# linear_supply3_smd.net
KiCad netlist of a schematic drawn in EAGLE
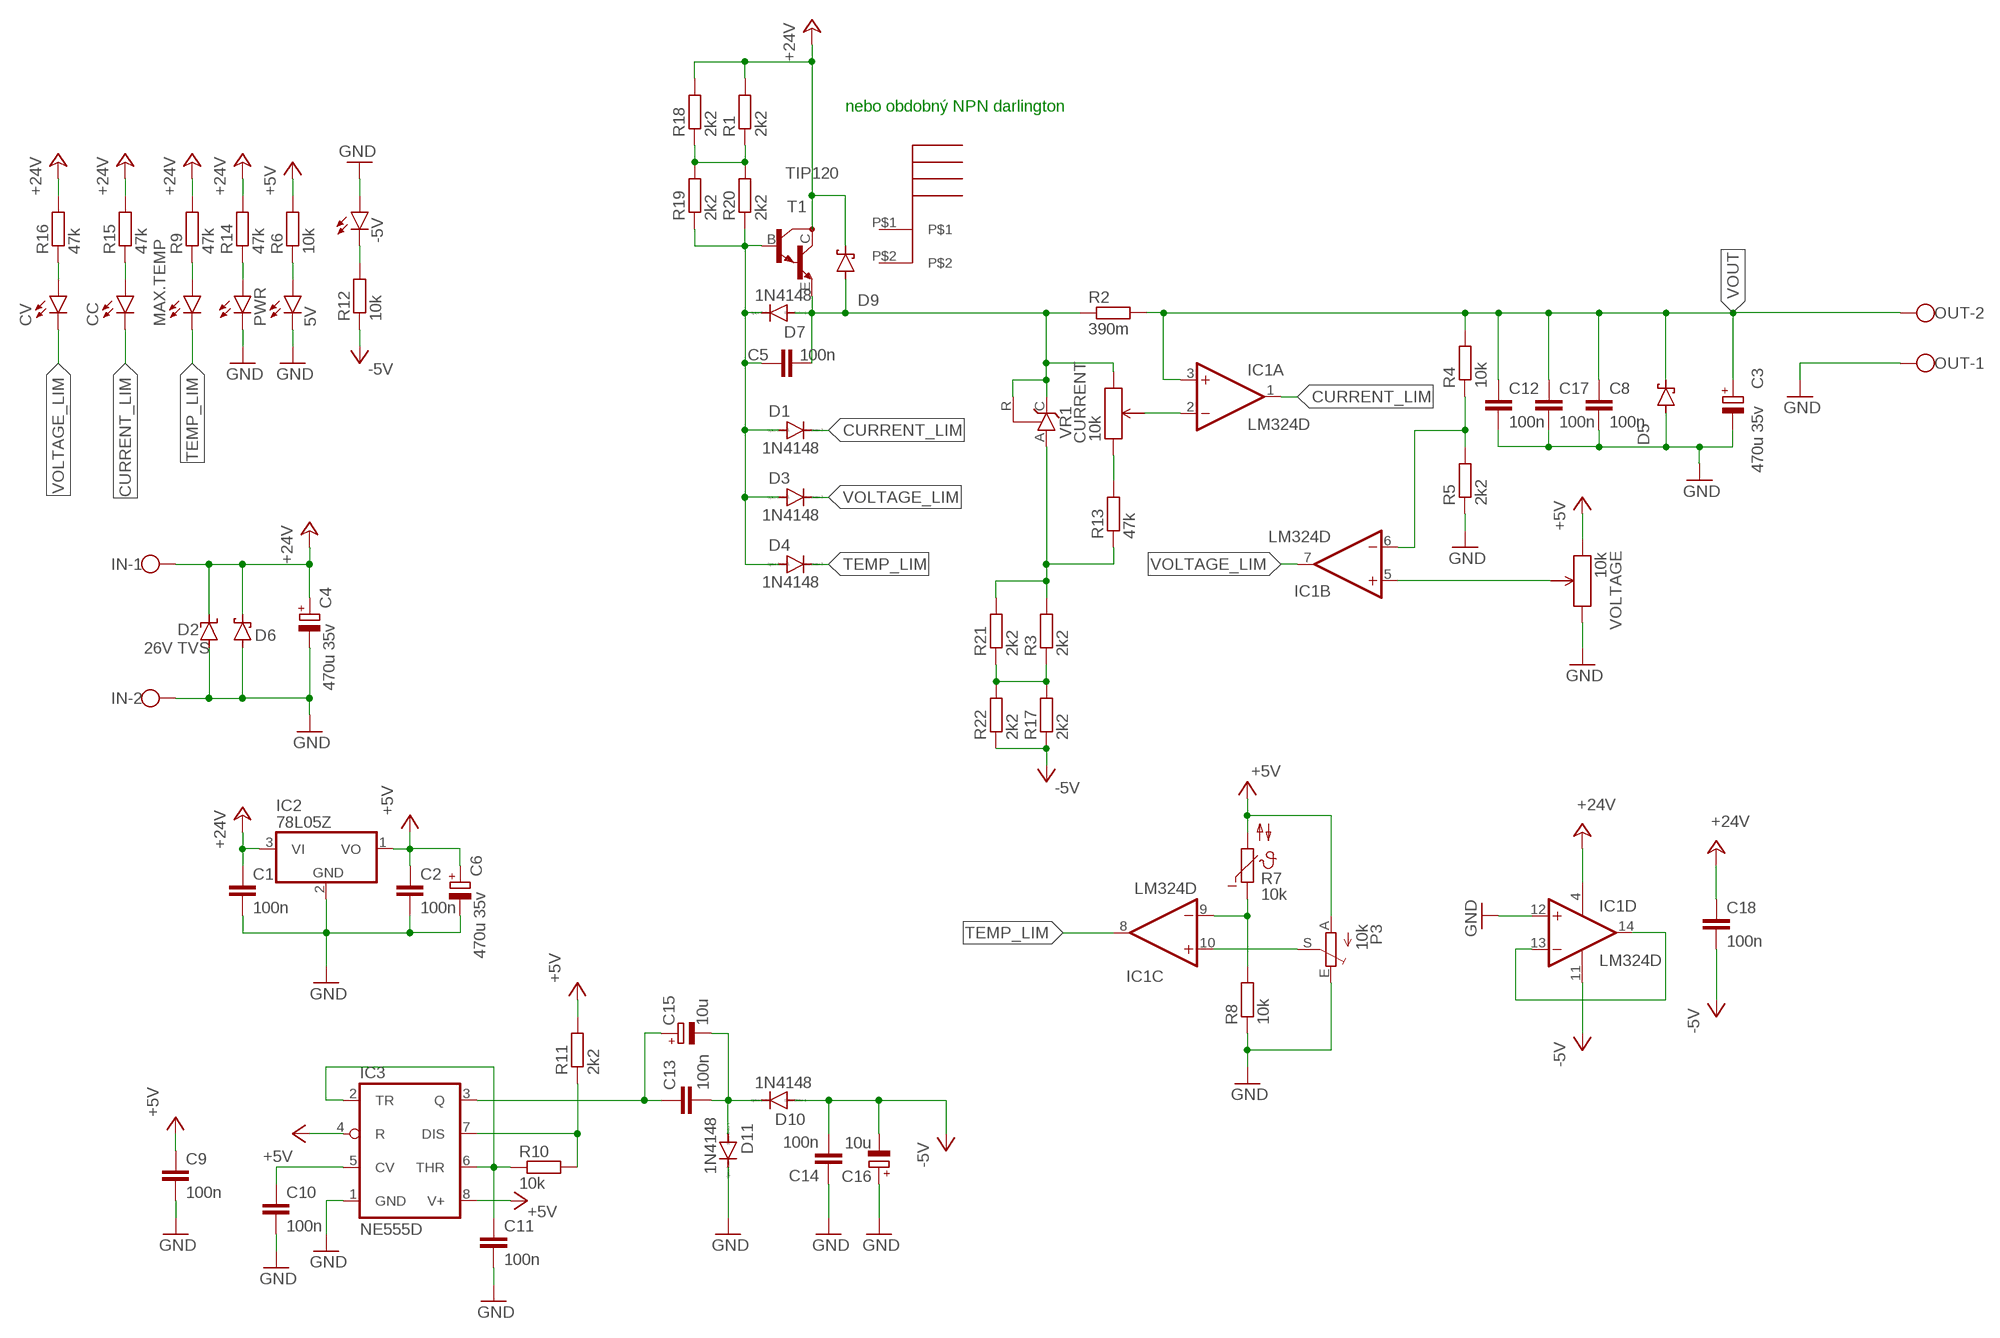
[diagram p0: schematic, sheet 1]

(export (version "E")
  (design (tool "Eeschema 10.0.6"))
  (components
    (comp (ref "-5V")
      (value "LEDCHIP-LED0805")
      (footprint "eagle-import:CHIP-LED0805")
      (libsource (lib "eagle-import") (part "LEDCHIP-LED0805"))
    )
    (comp (ref "5V")
      (value "LEDCHIP-LED0805")
      (footprint "eagle-import:CHIP-LED0805")
      (libsource (lib "eagle-import") (part "LEDCHIP-LED0805"))
    )
    (comp (ref "C1")
      (value "100n")
      (footprint "eagle-import:C0805")
      (libsource (lib "eagle-import") (part "C-EUC0805"))
    )
    (comp (ref "C2")
      (value "100n")
      (footprint "eagle-import:C0805")
      (libsource (lib "eagle-import") (part "C-EUC0805"))
    )
    (comp (ref "C3")
      (value "470u 35v")
      (footprint "eagle-import:E5-10,5")
      (libsource (lib "eagle-import") (part "CPOL-EUE5-10.5"))
    )
    (comp (ref "C4")
      (value "470u 35v")
      (footprint "eagle-import:E5-10,5")
      (libsource (lib "eagle-import") (part "CPOL-EUE5-10.5"))
    )
    (comp (ref "C5")
      (value "100n")
      (footprint "eagle-import:C0805")
      (libsource (lib "eagle-import") (part "C-EUC0805"))
    )
    (comp (ref "C6")
      (value "470u 35v")
      (footprint "eagle-import:E5-10,5")
      (libsource (lib "eagle-import") (part "CPOL-EUE5-10.5"))
    )
    (comp (ref "C8")
      (value "100n")
      (footprint "eagle-import:C050-050X075")
      (libsource (lib "eagle-import") (part "C-EU050-050X075"))
    )
    (comp (ref "C9")
      (value "100n")
      (footprint "eagle-import:C0805")
      (libsource (lib "eagle-import") (part "C-EUC0805"))
    )
    (comp (ref "C10")
      (value "100n")
      (footprint "eagle-import:C0805")
      (libsource (lib "eagle-import") (part "C-EUC0805"))
    )
    (comp (ref "C11")
      (value "100n")
      (footprint "eagle-import:C0805")
      (libsource (lib "eagle-import") (part "C-EUC0805"))
    )
    (comp (ref "C12")
      (value "100n")
      (footprint "eagle-import:C1206")
      (libsource (lib "eagle-import") (part "C-EUC1206"))
    )
    (comp (ref "C13")
      (value "100n")
      (footprint "eagle-import:C0805")
      (libsource (lib "eagle-import") (part "C-EUC0805"))
    )
    (comp (ref "C14")
      (value "100n")
      (footprint "eagle-import:C0805")
      (libsource (lib "eagle-import") (part "C-EUC0805"))
    )
    (comp (ref "C15")
      (value "10u")
      (footprint "eagle-import:E2,5-6")
      (libsource (lib "eagle-import") (part "CPOL-EUE2.5-6"))
    )
    (comp (ref "C16")
      (value "10u")
      (footprint "eagle-import:E2,5-6")
      (libsource (lib "eagle-import") (part "CPOL-EUE2.5-6"))
    )
    (comp (ref "C17")
      (value "100n")
      (footprint "eagle-import:C1206")
      (libsource (lib "eagle-import") (part "C-EUC1206"))
    )
    (comp (ref "C18")
      (value "100n")
      (footprint "eagle-import:C0805")
      (libsource (lib "eagle-import") (part "C-EUC0805"))
    )
    (comp (ref "CC")
      (value "LEDCHIP-LED0805")
      (footprint "eagle-import:CHIP-LED0805")
      (libsource (lib "eagle-import") (part "LEDCHIP-LED0805"))
    )
    (comp (ref "CURRENT")
      (value "10k")
      (footprint "eagle-import:THRU_PCW_POT")
      (libsource (lib "eagle-import") (part "THRU_PCB_POTKASO1"))
    )
    (comp (ref "CV")
      (value "LEDCHIP-LED0805")
      (footprint "eagle-import:CHIP-LED0805")
      (libsource (lib "eagle-import") (part "LEDCHIP-LED0805"))
    )
    (comp (ref "D1")
      (value "1N4148")
      (footprint "eagle-import:SOD80C")
      (libsource (lib "eagle-import") (part "PMLL4150"))
    )
    (comp (ref "D2")
      (value "26V TVS")
      (footprint "eagle-import:SMBJ")
      (libsource (lib "eagle-import") (part "SUPPRESSOR-SMBJ"))
    )
    (comp (ref "D3")
      (value "1N4148")
      (footprint "eagle-import:SOD80C")
      (libsource (lib "eagle-import") (part "PMLL4150"))
    )
    (comp (ref "D4")
      (value "1N4148")
      (footprint "eagle-import:SOD80C")
      (libsource (lib "eagle-import") (part "PMLL4150"))
    )
    (comp (ref "D5")
      (value "SCHOTTKY-DIODESMC")
      (footprint "eagle-import:SMC")
      (libsource (lib "eagle-import") (part "SCHOTTKY-DIODESMC"))
    )
    (comp (ref "D6")
      (value "SCHOTTKY-DIODESMC")
      (footprint "eagle-import:SMC")
      (libsource (lib "eagle-import") (part "SCHOTTKY-DIODESMC"))
    )
    (comp (ref "D7")
      (value "1N4148")
      (footprint "eagle-import:SOD80C")
      (libsource (lib "eagle-import") (part "PMLL4150"))
    )
    (comp (ref "D9")
      (value "SCHOTTKY-DIODESMC")
      (footprint "eagle-import:SMC")
      (libsource (lib "eagle-import") (part "SCHOTTKY-DIODESMC"))
    )
    (comp (ref "D10")
      (value "1N4148")
      (footprint "eagle-import:SOD80C")
      (libsource (lib "eagle-import") (part "PMLL4150"))
    )
    (comp (ref "D11")
      (value "1N4148")
      (footprint "eagle-import:SOD80C")
      (libsource (lib "eagle-import") (part "PMLL4150"))
    )
    (comp (ref "IC1")
      (value "LM324D")
      (footprint "eagle-import:SO14")
      (libsource (lib "eagle-import") (part "LM324D"))
    )
    (comp (ref "IC2")
      (value "78L05Z")
      (footprint "eagle-import:TO92")
      (libsource (lib "eagle-import") (part "78ZL05"))
    )
    (comp (ref "IC3")
      (value "NE555D")
      (footprint "eagle-import:SO08")
      (libsource (lib "eagle-import") (part "555DNE"))
    )
    (comp (ref "IN")
      (value "W237-102")
      (footprint "eagle-import:W237-102")
      (fields (field (name "MPN") "237-102"))
      (libsource (lib "eagle-import") (part "W237-102"))
    )
    (comp (ref "MAX.TEMP")
      (value "LEDCHIP-LED0805")
      (footprint "eagle-import:CHIP-LED0805")
      (libsource (lib "eagle-import") (part "LEDCHIP-LED0805"))
    )
    (comp (ref "OUT")
      (value "W237-102")
      (footprint "eagle-import:W237-102")
      (fields (field (name "MPN") "237-102"))
      (libsource (lib "eagle-import") (part "W237-102"))
    )
    (comp (ref "P3")
      (value "10k")
      (footprint "eagle-import:CA6V")
      (libsource (lib "eagle-import") (part "TRIM_EU-CA6V"))
    )
    (comp (ref "PWR")
      (value "LEDCHIP-LED0805")
      (footprint "eagle-import:CHIP-LED0805")
      (libsource (lib "eagle-import") (part "LEDCHIP-LED0805"))
    )
    (comp (ref "R1")
      (value "2k2")
      (footprint "eagle-import:R0805")
      (libsource (lib "eagle-import") (part "R-EU_R0805"))
    )
    (comp (ref "R2")
      (value "390m")
      (footprint "eagle-import:0411_12")
      (libsource (lib "eagle-import") (part "R-EU_0411/12"))
    )
    (comp (ref "R3")
      (value "2k2")
      (footprint "eagle-import:R0805")
      (libsource (lib "eagle-import") (part "R-EU_R0805"))
    )
    (comp (ref "R4")
      (value "10k")
      (footprint "eagle-import:R0805")
      (libsource (lib "eagle-import") (part "R-EU_R0805"))
    )
    (comp (ref "R5")
      (value "2k2")
      (footprint "eagle-import:R0805")
      (libsource (lib "eagle-import") (part "R-EU_R0805"))
    )
    (comp (ref "R6")
      (value "10k")
      (footprint "eagle-import:R0805")
      (libsource (lib "eagle-import") (part "R-EU_R0805"))
    )
    (comp (ref "R7")
      (value "10k")
      (footprint "eagle-import:P642")
      (libsource (lib "eagle-import") (part "V642"))
    )
    (comp (ref "R8")
      (value "10k")
      (footprint "eagle-import:R0805")
      (libsource (lib "eagle-import") (part "R-EU_R0805"))
    )
    (comp (ref "R9")
      (value "47k")
      (footprint "eagle-import:R0805")
      (libsource (lib "eagle-import") (part "R-EU_R0805"))
    )
    (comp (ref "R10")
      (value "10k")
      (footprint "eagle-import:R0805")
      (libsource (lib "eagle-import") (part "R-EU_R0805"))
    )
    (comp (ref "R11")
      (value "2k2")
      (footprint "eagle-import:R0805")
      (libsource (lib "eagle-import") (part "R-EU_R0805"))
    )
    (comp (ref "R12")
      (value "10k")
      (footprint "eagle-import:R0805")
      (libsource (lib "eagle-import") (part "R-EU_R0805"))
    )
    (comp (ref "R13")
      (value "47k")
      (footprint "eagle-import:R0805")
      (libsource (lib "eagle-import") (part "R-EU_R0805"))
    )
    (comp (ref "R14")
      (value "47k")
      (footprint "eagle-import:R0805")
      (libsource (lib "eagle-import") (part "R-EU_R0805"))
    )
    (comp (ref "R15")
      (value "47k")
      (footprint "eagle-import:R0805")
      (libsource (lib "eagle-import") (part "R-EU_R0805"))
    )
    (comp (ref "R16")
      (value "47k")
      (footprint "eagle-import:R0805")
      (libsource (lib "eagle-import") (part "R-EU_R0805"))
    )
    (comp (ref "R17")
      (value "2k2")
      (footprint "eagle-import:R0805")
      (libsource (lib "eagle-import") (part "R-EU_R0805"))
    )
    (comp (ref "R18")
      (value "2k2")
      (footprint "eagle-import:R0805")
      (libsource (lib "eagle-import") (part "R-EU_R0805"))
    )
    (comp (ref "R19")
      (value "2k2")
      (footprint "eagle-import:R0805")
      (libsource (lib "eagle-import") (part "R-EU_R0805"))
    )
    (comp (ref "R20")
      (value "2k2")
      (footprint "eagle-import:R0805")
      (libsource (lib "eagle-import") (part "R-EU_R0805"))
    )
    (comp (ref "R21")
      (value "2k2")
      (footprint "eagle-import:R0805")
      (libsource (lib "eagle-import") (part "R-EU_R0805"))
    )
    (comp (ref "R22")
      (value "2k2")
      (footprint "eagle-import:R0805")
      (libsource (lib "eagle-import") (part "R-EU_R0805"))
    )
    (comp (ref "T1")
      (value "TIP120")
      (footprint "eagle-import:SOT93")
      (libsource (lib "eagle-import") (part "BDV65"))
    )
    (comp (ref "U$1")
      (value "RAD-DY-KY/3")
      (footprint "eagle-import:RAD-DY-KY_3HEATSINK")
      (libsource (lib "eagle-import") (part "RAD-DY-KY/3"))
    )
    (comp (ref "VOLTAGE")
      (value "10k")
      (footprint "eagle-import:THRU_PCW_POT")
      (fields (field (name "SPICEPREFIX") "J"))
      (libsource (lib "eagle-import") (part "THRU_PCB_POTKASO1"))
    )
    (comp (ref "VR1")
      (value "TL431CLP")
      (footprint "eagle-import:TO92-CLP")
      (libsource (lib "eagle-import") (part "TL431CLP"))
    )
  )
  (nets
    (net (code "1") (name "+5V") (class "Default")
      (node (ref "C2") (pin "1") (pinfunction "1_1") (pintype "passive"))
      (node (ref "C6") (pin "+") (pinfunction "+_+") (pintype "passive"))
      (node (ref "C9") (pin "1") (pinfunction "1_1") (pintype "passive"))
      (node (ref "IC2") (pin "1") (pinfunction "VO_1") (pintype "passive"))
      (node (ref "IC3") (pin "4") (pinfunction "R_4") (pintype "input"))
      (node (ref "IC3") (pin "8") (pinfunction "V+_8") (pintype "power_in"))
      (node (ref "P3") (pin "A") (pinfunction "A_A") (pintype "passive"))
      (node (ref "R11") (pin "2") (pinfunction "2_2") (pintype "passive"))
      (node (ref "R6") (pin "2") (pinfunction "2_2") (pintype "passive"))
      (node (ref "R7") (pin "2") (pinfunction "2_2") (pintype "passive"))
      (node (ref "VOLTAGE") (pin "P$1") (pinfunction "1_P$1") (pintype "bidirectional"))
    )
    (net (code "2") (name "+24V") (class "Default")
      (node (ref "C1") (pin "1") (pinfunction "1_1") (pintype "passive"))
      (node (ref "C18") (pin "1") (pinfunction "1_1") (pintype "passive"))
      (node (ref "C4") (pin "+") (pinfunction "+_+") (pintype "passive"))
      (node (ref "D2") (pin "C") (pinfunction "C_C") (pintype "passive"))
      (node (ref "D6") (pin "C") (pinfunction "C_C") (pintype "passive"))
      (node (ref "D9") (pin "C") (pinfunction "C_C") (pintype "passive"))
      (node (ref "IC1") (pin "4") (pinfunction "V+_4") (pintype "power_in"))
      (node (ref "IC2") (pin "3") (pinfunction "VI_3") (pintype "input"))
      (node (ref "IN") (pin "1") (pinfunction "KL_1") (pintype "passive"))
      (node (ref "R1") (pin "2") (pinfunction "2_2") (pintype "passive"))
      (node (ref "R14") (pin "2") (pinfunction "2_2") (pintype "passive"))
      (node (ref "R15") (pin "2") (pinfunction "2_2") (pintype "passive"))
      (node (ref "R16") (pin "2") (pinfunction "2_2") (pintype "passive"))
      (node (ref "R18") (pin "2") (pinfunction "2_2") (pintype "passive"))
      (node (ref "R9") (pin "2") (pinfunction "2_2") (pintype "passive"))
      (node (ref "T1") (pin "C") (pinfunction "C_C") (pintype "passive"))
    )
    (net (code "3") (name "-5V") (class "Default")
      (node (ref "C14") (pin "2") (pinfunction "2_2") (pintype "passive"))
      (node (ref "C16") (pin "-") (pinfunction "-_-") (pintype "passive"))
      (node (ref "C18") (pin "2") (pinfunction "2_2") (pintype "passive"))
      (node (ref "D10") (pin "A") (pinfunction "A_A") (pintype "passive"))
      (node (ref "IC1") (pin "11") (pinfunction "V-_11") (pintype "power_in"))
      (node (ref "R12") (pin "1") (pinfunction "1_1") (pintype "passive"))
      (node (ref "R17") (pin "1") (pinfunction "1_1") (pintype "passive"))
      (node (ref "R22") (pin "1") (pinfunction "1_1") (pintype "passive"))
    )
    (net (code "4") (name "CURRENT_LIM") (class "Default")
      (node (ref "CC") (pin "C") (pinfunction "C_C") (pintype "passive"))
      (node (ref "D1") (pin "C") (pinfunction "C_C") (pintype "passive"))
      (node (ref "IC1") (pin "1") (pinfunction "OUT_1") (pintype "output"))
    )
    (net (code "5") (name "GND") (class "Default")
      (node (ref "-5V") (pin "A") (pinfunction "A_A") (pintype "passive"))
      (node (ref "5V") (pin "C") (pinfunction "C_C") (pintype "passive"))
      (node (ref "C1") (pin "2") (pinfunction "2_2") (pintype "passive"))
      (node (ref "C10") (pin "2") (pinfunction "2_2") (pintype "passive"))
      (node (ref "C11") (pin "2") (pinfunction "2_2") (pintype "passive"))
      (node (ref "C12") (pin "2") (pinfunction "2_2") (pintype "passive"))
      (node (ref "C14") (pin "1") (pinfunction "1_1") (pintype "passive"))
      (node (ref "C16") (pin "+") (pinfunction "+_+") (pintype "passive"))
      (node (ref "C17") (pin "2") (pinfunction "2_2") (pintype "passive"))
      (node (ref "C2") (pin "2") (pinfunction "2_2") (pintype "passive"))
      (node (ref "C3") (pin "-") (pinfunction "-_-") (pintype "passive"))
      (node (ref "C4") (pin "-") (pinfunction "-_-") (pintype "passive"))
      (node (ref "C6") (pin "-") (pinfunction "-_-") (pintype "passive"))
      (node (ref "C8") (pin "2") (pinfunction "2_2") (pintype "passive"))
      (node (ref "C9") (pin "2") (pinfunction "2_2") (pintype "passive"))
      (node (ref "D11") (pin "C") (pinfunction "C_C") (pintype "passive"))
      (node (ref "D2") (pin "A") (pinfunction "A_A") (pintype "passive"))
      (node (ref "D5") (pin "A") (pinfunction "A_A") (pintype "passive"))
      (node (ref "D6") (pin "A") (pinfunction "A_A") (pintype "passive"))
      (node (ref "IC1") (pin "12") (pinfunction "+IN_12") (pintype "input"))
      (node (ref "IC2") (pin "2") (pinfunction "GND_2") (pintype "passive"))
      (node (ref "IC3") (pin "1") (pinfunction "GND_1") (pintype "power_in"))
      (node (ref "IN") (pin "2") (pinfunction "KL_2") (pintype "passive"))
      (node (ref "OUT") (pin "1") (pinfunction "KL_1") (pintype "passive"))
      (node (ref "P3") (pin "E") (pinfunction "E_E") (pintype "passive"))
      (node (ref "PWR") (pin "C") (pinfunction "C_C") (pintype "passive"))
      (node (ref "R5") (pin "1") (pinfunction "1_1") (pintype "passive"))
      (node (ref "R8") (pin "1") (pinfunction "1_1") (pintype "passive"))
      (node (ref "VOLTAGE") (pin "P$3") (pinfunction "3_P$3") (pintype "bidirectional"))
    )
    (net (code "6") (name "Net-(-5V-PadC)") (class "Default")
      (node (ref "-5V") (pin "C") (pinfunction "C_C") (pintype "passive"))
      (node (ref "R12") (pin "2") (pinfunction "2_2") (pintype "passive"))
    )
    (net (code "7") (name "Net-(5V-PadA)") (class "Default")
      (node (ref "5V") (pin "A") (pinfunction "A_A") (pintype "passive"))
      (node (ref "R6") (pin "1") (pinfunction "1_1") (pintype "passive"))
    )
    (net (code "8") (name "Net-(C5-Pad1)") (class "Default")
      (node (ref "C5") (pin "1") (pinfunction "1_1") (pintype "passive"))
      (node (ref "D1") (pin "A") (pinfunction "A_A") (pintype "passive"))
      (node (ref "D3") (pin "A") (pinfunction "A_A") (pintype "passive"))
      (node (ref "D4") (pin "A") (pinfunction "A_A") (pintype "passive"))
      (node (ref "D7") (pin "C") (pinfunction "C_C") (pintype "passive"))
      (node (ref "R19") (pin "1") (pinfunction "1_1") (pintype "passive"))
      (node (ref "R20") (pin "1") (pinfunction "1_1") (pintype "passive"))
      (node (ref "T1") (pin "B") (pinfunction "B_B") (pintype "passive"))
    )
    (net (code "9") (name "Net-(C13-Pad2)") (class "Default")
      (node (ref "C13") (pin "2") (pinfunction "2_2") (pintype "passive"))
      (node (ref "C15") (pin "-") (pinfunction "-_-") (pintype "passive"))
      (node (ref "D10") (pin "C") (pinfunction "C_C") (pintype "passive"))
      (node (ref "D11") (pin "A") (pinfunction "A_A") (pintype "passive"))
    )
    (net (code "10") (name "Net-(CC-PadA)") (class "Default")
      (node (ref "CC") (pin "A") (pinfunction "A_A") (pintype "passive"))
      (node (ref "R15") (pin "1") (pinfunction "1_1") (pintype "passive"))
    )
    (net (code "11") (name "Net-(CURRENT-1)") (class "Default")
      (node (ref "CURRENT") (pin "P$1") (pinfunction "1_P$1") (pintype "bidirectional"))
      (node (ref "R13") (pin "2") (pinfunction "2_2") (pintype "passive"))
    )
    (net (code "12") (name "Net-(CURRENT-2)") (class "Default")
      (node (ref "CURRENT") (pin "P$2") (pinfunction "2_P$2") (pintype "bidirectional"))
      (node (ref "IC1") (pin "2") (pinfunction "-IN_2") (pintype "input"))
    )
    (net (code "13") (name "Net-(CURRENT-3)") (class "Default")
      (node (ref "C5") (pin "2") (pinfunction "2_2") (pintype "passive"))
      (node (ref "CURRENT") (pin "P$3") (pinfunction "3_P$3") (pintype "bidirectional"))
      (node (ref "D7") (pin "A") (pinfunction "A_A") (pintype "passive"))
      (node (ref "D9") (pin "A") (pinfunction "A_A") (pintype "passive"))
      (node (ref "R2") (pin "1") (pinfunction "1_1") (pintype "passive"))
      (node (ref "T1") (pin "E") (pinfunction "E_E") (pintype "passive"))
      (node (ref "VR1") (pin "C") (pinfunction "C_C") (pintype "passive"))
      (node (ref "VR1") (pin "R") (pinfunction "R_R") (pintype "passive"))
    )
    (net (code "14") (name "Net-(CV-PadA)") (class "Default")
      (node (ref "CV") (pin "A") (pinfunction "A_A") (pintype "passive"))
      (node (ref "R16") (pin "1") (pinfunction "1_1") (pintype "passive"))
    )
    (net (code "15") (name "Net-(IC1B-+IN)") (class "Default")
      (node (ref "IC1") (pin "5") (pinfunction "+IN_5") (pintype "input"))
      (node (ref "VOLTAGE") (pin "P$2") (pinfunction "2_P$2") (pintype "bidirectional"))
    )
    (net (code "16") (name "Net-(IC1B--IN)") (class "Default")
      (node (ref "IC1") (pin "6") (pinfunction "-IN_6") (pintype "input"))
      (node (ref "R4") (pin "1") (pinfunction "1_1") (pintype "passive"))
      (node (ref "R5") (pin "2") (pinfunction "2_2") (pintype "passive"))
    )
    (net (code "17") (name "Net-(IC1C-+IN)") (class "Default")
      (node (ref "IC1") (pin "10") (pinfunction "+IN_10") (pintype "input"))
      (node (ref "P3") (pin "S") (pinfunction "S_S") (pintype "passive"))
    )
    (net (code "18") (name "Net-(IC1C--IN)") (class "Default")
      (node (ref "IC1") (pin "9") (pinfunction "-IN_9") (pintype "input"))
      (node (ref "R7") (pin "1") (pinfunction "1_1") (pintype "passive"))
      (node (ref "R8") (pin "2") (pinfunction "2_2") (pintype "passive"))
    )
    (net (code "19") (name "Net-(IC1D--IN)") (class "Default")
      (node (ref "IC1") (pin "13") (pinfunction "-IN_13") (pintype "input"))
      (node (ref "IC1") (pin "14") (pinfunction "OUT_14") (pintype "output"))
    )
    (net (code "20") (name "Net-(IC3-CV)") (class "Default")
      (node (ref "C10") (pin "1") (pinfunction "1_1") (pintype "passive"))
      (node (ref "IC3") (pin "5") (pinfunction "CV_5") (pintype "input"))
    )
    (net (code "21") (name "Net-(IC3-DIS)") (class "Default")
      (node (ref "IC3") (pin "7") (pinfunction "DIS_7") (pintype "input"))
      (node (ref "R10") (pin "2") (pinfunction "2_2") (pintype "passive"))
      (node (ref "R11") (pin "1") (pinfunction "1_1") (pintype "passive"))
    )
    (net (code "22") (name "Net-(IC3-Q)") (class "Default")
      (node (ref "C13") (pin "1") (pinfunction "1_1") (pintype "passive"))
      (node (ref "C15") (pin "+") (pinfunction "+_+") (pintype "passive"))
      (node (ref "IC3") (pin "3") (pinfunction "Q_3") (pintype "output"))
    )
    (net (code "23") (name "Net-(IC3-THR)") (class "Default")
      (node (ref "C11") (pin "1") (pinfunction "1_1") (pintype "passive"))
      (node (ref "IC3") (pin "2") (pinfunction "TR_2") (pintype "input"))
      (node (ref "IC3") (pin "6") (pinfunction "THR_6") (pintype "input"))
      (node (ref "R10") (pin "1") (pinfunction "1_1") (pintype "passive"))
    )
    (net (code "24") (name "Net-(MAX.TEMP-PadA)") (class "Default")
      (node (ref "MAX.TEMP") (pin "A") (pinfunction "A_A") (pintype "passive"))
      (node (ref "R9") (pin "1") (pinfunction "1_1") (pintype "passive"))
    )
    (net (code "25") (name "Net-(PWR-PadA)") (class "Default")
      (node (ref "PWR") (pin "A") (pinfunction "A_A") (pintype "passive"))
      (node (ref "R14") (pin "1") (pinfunction "1_1") (pintype "passive"))
    )
    (net (code "26") (name "Net-(R1-Pad1)") (class "Default")
      (node (ref "R1") (pin "1") (pinfunction "1_1") (pintype "passive"))
      (node (ref "R18") (pin "1") (pinfunction "1_1") (pintype "passive"))
      (node (ref "R19") (pin "2") (pinfunction "2_2") (pintype "passive"))
      (node (ref "R20") (pin "2") (pinfunction "2_2") (pintype "passive"))
    )
    (net (code "27") (name "Net-(R13-Pad1)") (class "Default")
      (node (ref "R13") (pin "1") (pinfunction "1_1") (pintype "passive"))
      (node (ref "R21") (pin "2") (pinfunction "2_2") (pintype "passive"))
      (node (ref "R3") (pin "2") (pinfunction "2_2") (pintype "passive"))
      (node (ref "VR1") (pin "A") (pinfunction "A_A") (pintype "passive"))
    )
    (net (code "28") (name "Net-(R17-Pad2)") (class "Default")
      (node (ref "R17") (pin "2") (pinfunction "2_2") (pintype "passive"))
      (node (ref "R21") (pin "1") (pinfunction "1_1") (pintype "passive"))
      (node (ref "R22") (pin "2") (pinfunction "2_2") (pintype "passive"))
      (node (ref "R3") (pin "1") (pinfunction "1_1") (pintype "passive"))
    )
    (net (code "29") (name "TEMP_LIM") (class "Default")
      (node (ref "D4") (pin "C") (pinfunction "C_C") (pintype "passive"))
      (node (ref "IC1") (pin "8") (pinfunction "OUT_8") (pintype "output"))
      (node (ref "MAX.TEMP") (pin "C") (pinfunction "C_C") (pintype "passive"))
    )
    (net (code "30") (name "VOLTAGE_LIM") (class "Default")
      (node (ref "CV") (pin "C") (pinfunction "C_C") (pintype "passive"))
      (node (ref "D3") (pin "C") (pinfunction "C_C") (pintype "passive"))
      (node (ref "IC1") (pin "7") (pinfunction "OUT_7") (pintype "output"))
    )
    (net (code "31") (name "VOUT") (class "Default")
      (node (ref "C12") (pin "1") (pinfunction "1_1") (pintype "passive"))
      (node (ref "C17") (pin "1") (pinfunction "1_1") (pintype "passive"))
      (node (ref "C3") (pin "+") (pinfunction "+_+") (pintype "passive"))
      (node (ref "C8") (pin "1") (pinfunction "1_1") (pintype "passive"))
      (node (ref "D5") (pin "C") (pinfunction "C_C") (pintype "passive"))
      (node (ref "IC1") (pin "3") (pinfunction "+IN_3") (pintype "input"))
      (node (ref "OUT") (pin "2") (pinfunction "KL_2") (pintype "passive"))
      (node (ref "R2") (pin "2") (pinfunction "2_2") (pintype "passive"))
      (node (ref "R4") (pin "2") (pinfunction "2_2") (pintype "passive"))
    )
    (net (code "32") (name "unconnected-(U$1-PadP$1)") (class "Default")
      (node (ref "U$1") (pin "P$1") (pinfunction "P$1_P$1") (pintype "bidirectional"))
    )
    (net (code "33") (name "unconnected-(U$1-PadP$2)") (class "Default")
      (node (ref "U$1") (pin "P$2") (pinfunction "P$2_P$2") (pintype "bidirectional"))
    )
  )
)
